# Mic.net
KiCad netlist of a schematic drawn in Altium Designer
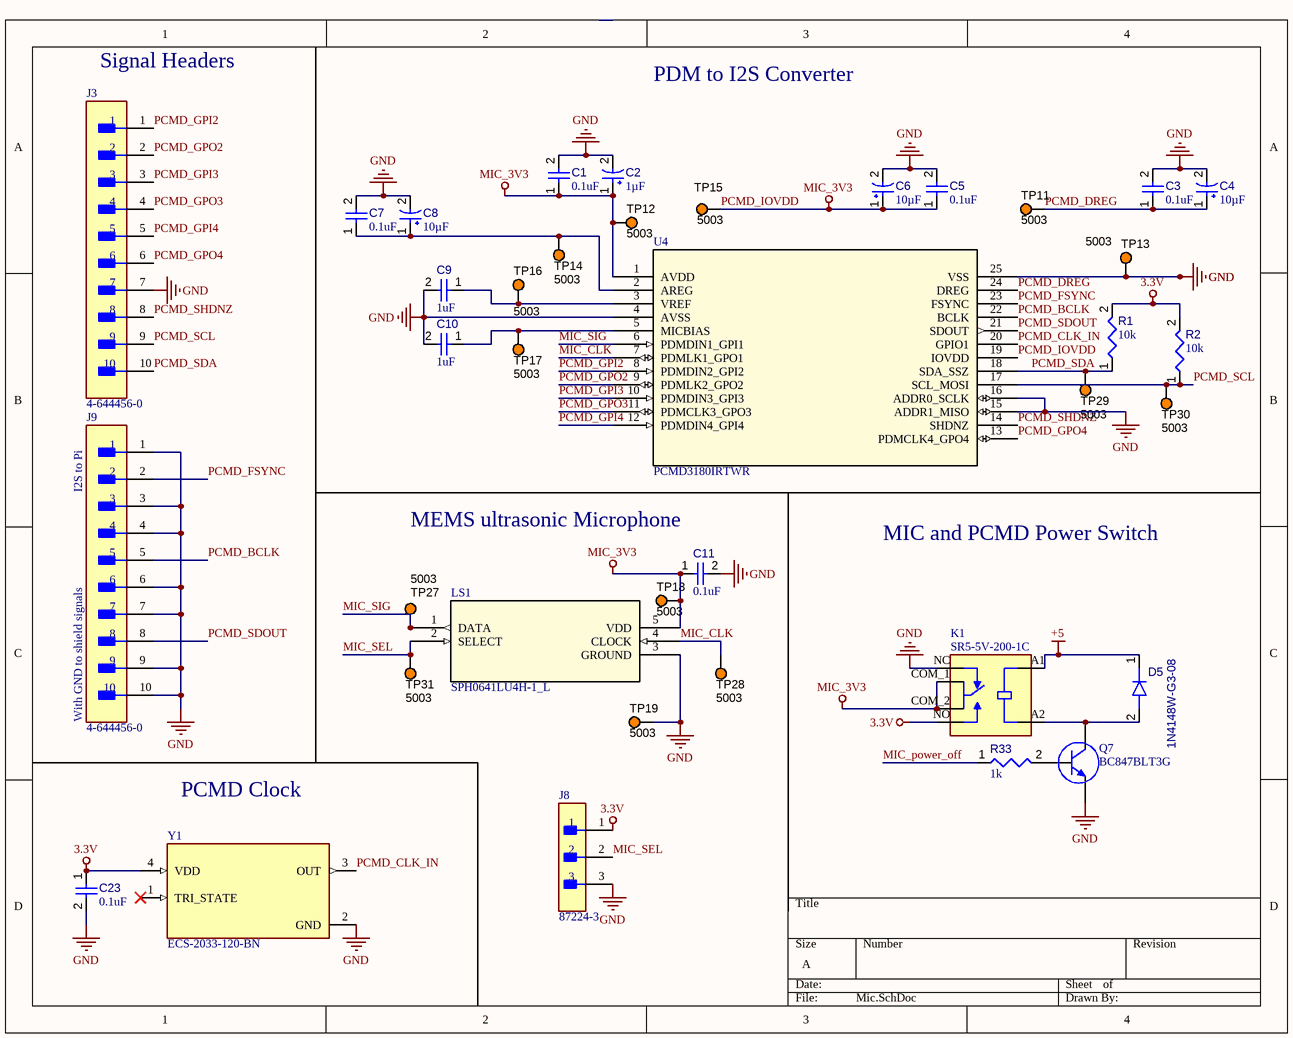
[diagram p0: Mic.SchDoc]

(export (version "E")
  (design (tool "Eeschema 10.0.6"))
  (components
    (comp (ref "C1")
      (value "0.1uF")
      (footprint "CAPC1608X90X40NL10T20")
      (description "Chip Capacitor, 100 nF, +/- 10%, 50 V, 0603 (1608 Metric)")
      (fields (field (name "TOLERANCE") "10%") (field (name "Comment") "Capacitor 100 nF +/-10% 50 V 0603"))
      (libsource (lib "University of Michigan") (part "CAP-NP-2"))
    )
    (comp (ref "C2")
      (value "1µF")
      (footprint "CAPPR55-200-1100X500X1200")
      (description "Aluminum Electrolytic Capacitor, 1 uF, +/- 20%, 50 V, -55 to 105 degC, 2-Pin THD, RoHS, Bulk")
      (fields (field (name "TOLERANCE") "20%") (field (name "MANUFACTURER") "Panasonic"))
      (libsource (lib "University of Michigan") (part "CAP-P-2"))
    )
    (comp (ref "C3")
      (value "0.1uF")
      (footprint "CAPC1608X90X40NL10T20")
      (description "Chip Capacitor, 100 nF, +/- 10%, 50 V, 0603 (1608 Metric)")
      (fields (field (name "TOLERANCE") "10%") (field (name "Comment") "Capacitor 100 nF +/-10% 50 V 0603"))
      (libsource (lib "University of Michigan") (part "CAP-NP-2"))
    )
    (comp (ref "C4")
      (value "10µF")
      (footprint "CAPPR55-200-1100X500X1200")
      (description "Aluminum Electrolytic Capacitor, 1 uF, +/- 20%, 50 V, -55 to 105 degC, 2-Pin THD, RoHS, Bulk")
      (fields (field (name "TOLERANCE") "20%") (field (name "MANUFACTURER") "Panasonic"))
      (libsource (lib "University of Michigan") (part "CAP-P-2"))
    )
    (comp (ref "C5")
      (value "0.1uF")
      (footprint "CAPC1608X90X40NL10T20")
      (description "Chip Capacitor, 100 nF, +/- 10%, 50 V, 0603 (1608 Metric)")
      (fields (field (name "TOLERANCE") "10%") (field (name "Comment") "Capacitor 100 nF +/-10% 50 V 0603"))
      (libsource (lib "University of Michigan") (part "CAP-NP-2"))
    )
    (comp (ref "C6")
      (value "10µF")
      (footprint "CAPPR55-200-1100X500X1200")
      (description "Aluminum Electrolytic Capacitor, 1 uF, +/- 20%, 50 V, -55 to 105 degC, 2-Pin THD, RoHS, Bulk")
      (fields (field (name "TOLERANCE") "20%") (field (name "MANUFACTURER") "Panasonic"))
      (libsource (lib "") (part "CAP-P-2_1"))
    )
    (comp (ref "C7")
      (value "0.1uF")
      (footprint "CAPC1608X90X40NL10T20")
      (description "Chip Capacitor, 100 nF, +/- 10%, 50 V, 0603 (1608 Metric)")
      (fields (field (name "TOLERANCE") "10%") (field (name "Comment") "Capacitor 100 nF +/-10% 50 V 0603"))
      (libsource (lib "University of Michigan") (part "CAP-NP-2"))
    )
    (comp (ref "C8")
      (value "10µF")
      (footprint "CAPPR55-200-1100X500X1200")
      (description "Aluminum Electrolytic Capacitor, 1 uF, +/- 20%, 50 V, -55 to 105 degC, 2-Pin THD, RoHS, Bulk")
      (fields (field (name "TOLERANCE") "20%") (field (name "MANUFACTURER") "Panasonic"))
      (libsource (lib "University of Michigan") (part "CAP-P-2"))
    )
    (comp (ref "C9")
      (value "1uF")
      (footprint "CAPC1608X90X40NL10T20")
      (description "Chip Capacitor, 100 nF, +/- 10%, 50 V, 0603 (1608 Metric)")
      (fields (field (name "TOLERANCE") "10%") (field (name "Comment") "Capacitor 100 nF +/-10% 50 V 0603"))
      (libsource (lib "University of Michigan") (part "CAP-NP-2"))
    )
    (comp (ref "C10")
      (value "1uF")
      (footprint "CAPC1608X90X40NL10T20")
      (description "Chip Capacitor, 100 nF, +/- 10%, 50 V, 0603 (1608 Metric)")
      (fields (field (name "TOLERANCE") "10%") (field (name "Comment") "Capacitor 100 nF +/-10% 50 V 0603"))
      (libsource (lib "University of Michigan") (part "CAP-NP-2"))
    )
    (comp (ref "C11")
      (value "0.1uF")
      (footprint "CAPC1608X90X40NL10T20")
      (description "Chip Capacitor, 100 nF, +/- 10%, 50 V, 0603 (1608 Metric)")
      (fields (field (name "TOLERANCE") "10%") (field (name "Comment") "Capacitor 100 nF +/-10% 50 V 0603"))
      (libsource (lib "University of Michigan") (part "CAP-NP-2"))
    )
    (comp (ref "C23")
      (value "0.1uF")
      (footprint "CAPC1608X90X40NL10T20")
      (description "Chip Capacitor, 100 nF, +/- 10%, 50 V, 0603 (1608 Metric)")
      (fields (field (name "TOLERANCE") "10%") (field (name "Comment") "Capacitor 100 nF +/-10% 50 V 0603"))
      (libsource (lib "University of Michigan") (part "CAP-NP-2"))
    )
    (comp (ref "D5")
      (value "1N4148W-G3-08")
      (footprint "FP-S8-V-3910_01-001-IPC_B")
      (description "Rectifier Diode, 1 Phase, 1 Element, 0.15A, 100V V(RRM), Silicon")
      (libsource (lib "University of Michigan") (part "DIODE-2"))
    )
    (comp (ref "J3")
      (value "4-644456-0")
      (footprint "FP-4-644456-0-MFG")
      (libsource (lib "University of Michigan") (part "aee40dc8b284c03a16094555aa210be"))
    )
    (comp (ref "J8")
      (value "87224-3")
      (footprint "FP-87224-3-MFG")
      (libsource (lib "University of Michigan") (part "0d3f023dd272f625e17a2be33dea85f"))
    )
    (comp (ref "J9")
      (value "4-644456-0")
      (footprint "FP-4-644456-0-MFG")
      (libsource (lib "University of Michigan") (part "aee40dc8b284c03a16094555aa210be"))
    )
    (comp (ref "K1")
      (value "SR5-5V-200-1C")
      (footprint "RELAY_SR5-5V-200-1C")
      (description "15.6 x 10.6 x 11.8 mm, 5 V, 1 A, SPDT (1 Form C), Through Hole, Signal Relay")
      (fields (field (name "MF") "CUI Devices"))
      (libsource (lib "University of Michigan") (part "SR5-5V-200-1C"))
    )
    (comp (ref "LS1")
      (value "SPH0641LU4H-1_L")
      (footprint "SPH0655LM4H-1_KNO_L")
      (description "No Description Available")
      (fields
        (field (name "MANUFACTURER_PART_NUMBER") "SPH0641LU4H-1")
        (field (name "COPYRIGHT") "Copyright (C) 2023 Ultra Librarian. All rights reserved.")
      )
      (libsource (lib "University of Michigan") (part "SPH0641LU4H-1_L"))
    )
    (comp (ref "Q7")
      (value "BC847BLT3G")
      (footprint "ONSC-SOT-23-3-318-08_V")
      (description "Small Signal Bipolar Transistor, 0.1A I(C), 45V V(BR)CEO, 1-Element, NPN, Silicon, TO-236")
      (libsource (lib "University of Michigan") (part "TRANS-NPN-3"))
    )
    (comp (ref "R1")
      (value "10k")
      (footprint "RESC0603(1608)_L")
      (description "Chip Resistor, 120 Ohms, +/-5 %, 0.1 W, -55 to 155 degC, 0603")
      (fields (field (name "POWER") "100mW") (field (name "TOLERANCE") "5%"))
      (libsource (lib "University of Michigan") (part "RES-2"))
    )
    (comp (ref "R2")
      (value "10k")
      (footprint "RESC0603(1608)_L")
      (description "Chip Resistor, 120 Ohms, +/-5 %, 0.1 W, -55 to 155 degC, 0603")
      (fields (field (name "POWER") "100mW") (field (name "TOLERANCE") "5%"))
      (libsource (lib "University of Michigan") (part "RES-2"))
    )
    (comp (ref "R33")
      (value "1k")
      (footprint "RESC0603(1608)_L")
      (description "Chip Resistor, 120 Ohms, +/-5 %, 0.1 W, -55 to 155 degC, 0603")
      (fields (field (name "POWER") "100mW") (field (name "TOLERANCE") "5%"))
      (libsource (lib "University of Michigan") (part "RES-2"))
    )
    (comp (ref "TP11")
      (value "5003")
      (footprint "KSTN-5003")
      (description "Test Point, Orange, Height 4.6 mm, Tail Length 3 mm, 1-Pin THD, RoHS")
      (fields (field (name "MANUFACTURER") "Keystone"))
      (libsource (lib "University of Michigan") (part "TESTPOINT_ORANGE"))
    )
    (comp (ref "TP12")
      (value "5003")
      (footprint "KSTN-5003")
      (description "Test Point, Orange, Height 4.6 mm, Tail Length 3 mm, 1-Pin THD, RoHS")
      (fields (field (name "MANUFACTURER") "Keystone"))
      (libsource (lib "University of Michigan") (part "TESTPOINT_ORANGE"))
    )
    (comp (ref "TP13")
      (value "5003")
      (footprint "KSTN-5003")
      (description "Test Point, Orange, Height 4.6 mm, Tail Length 3 mm, 1-Pin THD, RoHS")
      (fields (field (name "MANUFACTURER") "Keystone"))
      (libsource (lib "University of Michigan") (part "TESTPOINT_ORANGE"))
    )
    (comp (ref "TP14")
      (value "5003")
      (footprint "KSTN-5003")
      (description "Test Point, Orange, Height 4.6 mm, Tail Length 3 mm, 1-Pin THD, RoHS")
      (fields (field (name "MANUFACTURER") "Keystone"))
      (libsource (lib "University of Michigan") (part "TESTPOINT_ORANGE"))
    )
    (comp (ref "TP15")
      (value "5003")
      (footprint "KSTN-5003")
      (description "Test Point, Orange, Height 4.6 mm, Tail Length 3 mm, 1-Pin THD, RoHS")
      (fields (field (name "MANUFACTURER") "Keystone"))
      (libsource (lib "University of Michigan") (part "TESTPOINT_ORANGE"))
    )
    (comp (ref "TP16")
      (value "5003")
      (footprint "KSTN-5003")
      (description "Test Point, Orange, Height 4.6 mm, Tail Length 3 mm, 1-Pin THD, RoHS")
      (fields (field (name "MANUFACTURER") "Keystone"))
      (libsource (lib "University of Michigan") (part "TESTPOINT_ORANGE"))
    )
    (comp (ref "TP17")
      (value "5003")
      (footprint "KSTN-5003")
      (description "Test Point, Orange, Height 4.6 mm, Tail Length 3 mm, 1-Pin THD, RoHS")
      (fields (field (name "MANUFACTURER") "Keystone"))
      (libsource (lib "University of Michigan") (part "TESTPOINT_ORANGE"))
    )
    (comp (ref "TP18")
      (value "5003")
      (footprint "KSTN-5003")
      (description "Test Point, Orange, Height 4.6 mm, Tail Length 3 mm, 1-Pin THD, RoHS")
      (fields (field (name "MANUFACTURER") "Keystone"))
      (libsource (lib "University of Michigan") (part "TESTPOINT_ORANGE"))
    )
    (comp (ref "TP19")
      (value "5003")
      (footprint "KSTN-5003")
      (description "Test Point, Orange, Height 4.6 mm, Tail Length 3 mm, 1-Pin THD, RoHS")
      (fields (field (name "MANUFACTURER") "Keystone"))
      (libsource (lib "University of Michigan") (part "TESTPOINT_ORANGE"))
    )
    (comp (ref "TP27")
      (value "5003")
      (footprint "KSTN-5003")
      (description "Test Point, Orange, Height 4.6 mm, Tail Length 3 mm, 1-Pin THD, RoHS")
      (fields (field (name "MANUFACTURER") "Keystone"))
      (libsource (lib "University of Michigan") (part "TESTPOINT_ORANGE"))
    )
    (comp (ref "TP28")
      (value "5003")
      (footprint "KSTN-5003")
      (description "Test Point, Orange, Height 4.6 mm, Tail Length 3 mm, 1-Pin THD, RoHS")
      (fields (field (name "MANUFACTURER") "Keystone"))
      (libsource (lib "University of Michigan") (part "TESTPOINT_ORANGE"))
    )
    (comp (ref "TP29")
      (value "5003")
      (footprint "KSTN-5003")
      (description "Test Point, Orange, Height 4.6 mm, Tail Length 3 mm, 1-Pin THD, RoHS")
      (fields (field (name "MANUFACTURER") "Keystone"))
      (libsource (lib "University of Michigan") (part "TESTPOINT_ORANGE"))
    )
    (comp (ref "TP30")
      (value "5003")
      (footprint "KSTN-5003")
      (description "Test Point, Orange, Height 4.6 mm, Tail Length 3 mm, 1-Pin THD, RoHS")
      (fields (field (name "MANUFACTURER") "Keystone"))
      (libsource (lib "University of Michigan") (part "TESTPOINT_ORANGE"))
    )
    (comp (ref "TP31")
      (value "5003")
      (footprint "KSTN-5003")
      (description "Test Point, Orange, Height 4.6 mm, Tail Length 3 mm, 1-Pin THD, RoHS")
      (fields (field (name "MANUFACTURER") "Keystone"))
      (libsource (lib "University of Michigan") (part "TESTPOINT_ORANGE"))
    )
    (comp (ref "U4")
      (value "PCMD3180IRTWR")
      (footprint "QFN_0IRTWR_TEX")
      (description "No Description Available")
      (fields (field (name "COPYRIGHT") "Copyright (C) 2023 Ultra Librarian. All rights reserved."))
      (libsource (lib "University of Michigan") (part "PCMD3180IRTWR"))
    )
    (comp (ref "Y1")
      (value "ECS-2033-120-BN")
      (footprint "OSC_ECS-2033-120-BN")
      (description "12MHz XO (Standard) CMOS Oscillator 3.3V Enable/Disable 4-SMD, No Lead")
      (fields (field (name "MF") "ECS Inc."))
      (libsource (lib "University of Michigan") (part "ECS-2033-120-BN"))
    )
  )
  (nets
    (net (code "1") (name "+5") (class "Default")
      (node (ref "D5") (pin "1") (pinfunction "K_1") (pintype "passive"))
      (node (ref "K1") (pin "A1") (pinfunction "COIL1_A1") (pintype "passive"))
    )
    (net (code "2") (name "/MIC_CLK") (class "Default")
      (node (ref "LS1") (pin "4") (pinfunction "CLOCK_4") (pintype "input"))
      (node (ref "TP28") (pin "1") (pinfunction "1_1") (pintype "passive"))
      (node (ref "U4") (pin "7") (pinfunction "PDMLK1_GPO1_7") (pintype "bidirectional"))
    )
    (net (code "3") (name "/MIC_SEL") (class "Default")
      (node (ref "J8") (pin "2") (pinfunction "2_2") (pintype "passive"))
      (node (ref "LS1") (pin "2") (pinfunction "SELECT_2") (pintype "input"))
      (node (ref "TP31") (pin "1") (pinfunction "1_1") (pintype "passive"))
    )
    (net (code "4") (name "/MIC_SIG") (class "Default")
      (node (ref "LS1") (pin "1") (pinfunction "DATA_1") (pintype "output"))
      (node (ref "TP27") (pin "1") (pinfunction "1_1") (pintype "passive"))
      (node (ref "U4") (pin "6") (pinfunction "PDMDIN1_GPI1_6") (pintype "input"))
    )
    (net (code "5") (name "/MIC_power_off") (class "Default")
      (node (ref "R33") (pin "1") (pinfunction "1_1") (pintype "passive"))
    )
    (net (code "6") (name "/PCMD_BCLK") (class "Default")
      (node (ref "J9") (pin "5") (pinfunction "5_5") (pintype "passive"))
      (node (ref "U4") (pin "22") (pinfunction "BCLK_22") (pintype "passive"))
    )
    (net (code "7") (name "/PCMD_CLK_IN") (class "Default")
      (node (ref "U4") (pin "20") (pinfunction "GPIO1_20") (pintype "passive"))
      (node (ref "Y1") (pin "3") (pinfunction "OUT_3") (pintype "output"))
    )
    (net (code "8") (name "/PCMD_DREG") (class "Default")
      (node (ref "C3") (pin "1") (pinfunction "1_1") (pintype "passive"))
      (node (ref "C4") (pin "1") (pinfunction "1_1") (pintype "passive"))
      (node (ref "TP11") (pin "1") (pinfunction "1_1") (pintype "passive"))
      (node (ref "U4") (pin "24") (pinfunction "DREG_24") (pintype "passive"))
    )
    (net (code "9") (name "/PCMD_FSYNC") (class "Default")
      (node (ref "J9") (pin "2") (pinfunction "2_2") (pintype "passive"))
      (node (ref "U4") (pin "23") (pinfunction "FSYNC_23") (pintype "passive"))
    )
    (net (code "10") (name "/PCMD_GPI2") (class "Default")
      (node (ref "J3") (pin "1") (pinfunction "1_1") (pintype "passive"))
      (node (ref "U4") (pin "8") (pinfunction "PDMDIN2_GPI2_8") (pintype "input"))
    )
    (net (code "11") (name "/PCMD_GPI3") (class "Default")
      (node (ref "J3") (pin "3") (pinfunction "3_3") (pintype "passive"))
      (node (ref "U4") (pin "10") (pinfunction "PDMDIN3_GPI3_10") (pintype "input"))
    )
    (net (code "12") (name "/PCMD_GPI4") (class "Default")
      (node (ref "J3") (pin "5") (pinfunction "5_5") (pintype "passive"))
      (node (ref "U4") (pin "12") (pinfunction "PDMDIN4_GPI4_12") (pintype "input"))
    )
    (net (code "13") (name "/PCMD_GPO2") (class "Default")
      (node (ref "J3") (pin "2") (pinfunction "2_2") (pintype "passive"))
      (node (ref "U4") (pin "9") (pinfunction "PDMLK2_GPO2_9") (pintype "bidirectional"))
    )
    (net (code "14") (name "/PCMD_GPO3") (class "Default")
      (node (ref "J3") (pin "4") (pinfunction "4_4") (pintype "passive"))
      (node (ref "U4") (pin "11") (pinfunction "PDMCLK3_GPO3_11") (pintype "bidirectional"))
    )
    (net (code "15") (name "/PCMD_GPO4") (class "Default")
      (node (ref "J3") (pin "6") (pinfunction "6_6") (pintype "passive"))
      (node (ref "U4") (pin "13") (pinfunction "PDMCLK4_GPO4_13") (pintype "bidirectional"))
    )
    (net (code "16") (name "/PCMD_SCL") (class "Default")
      (node (ref "J3") (pin "9") (pinfunction "9_9") (pintype "passive"))
      (node (ref "R2") (pin "1") (pinfunction "1_1") (pintype "passive"))
      (node (ref "TP30") (pin "1") (pinfunction "1_1") (pintype "passive"))
      (node (ref "U4") (pin "17") (pinfunction "SCL_MOSI_17") (pintype "passive"))
    )
    (net (code "17") (name "/PCMD_SDA") (class "Default")
      (node (ref "J3") (pin "10") (pinfunction "10_10") (pintype "passive"))
      (node (ref "R1") (pin "1") (pinfunction "1_1") (pintype "passive"))
      (node (ref "TP29") (pin "1") (pinfunction "1_1") (pintype "passive"))
      (node (ref "U4") (pin "18") (pinfunction "SDA_SSZ_18") (pintype "passive"))
    )
    (net (code "18") (name "/PCMD_SDOUT") (class "Default")
      (node (ref "J9") (pin "8") (pinfunction "8_8") (pintype "passive"))
      (node (ref "U4") (pin "21") (pinfunction "SDOUT_21") (pintype "output"))
    )
    (net (code "19") (name "/PCMD_SHDNZ") (class "Default")
      (node (ref "J3") (pin "8") (pinfunction "8_8") (pintype "passive"))
      (node (ref "U4") (pin "14") (pinfunction "SHDNZ_14") (pintype "passive"))
    )
    (net (code "20") (name "3.3V") (class "Default")
      (node (ref "C23") (pin "1") (pinfunction "1_1") (pintype "passive"))
      (node (ref "J8") (pin "1") (pinfunction "1_1") (pintype "passive"))
      (node (ref "K1") (pin "NO") (pinfunction "NO_NO") (pintype "passive"))
      (node (ref "R1") (pin "2") (pinfunction "2_2") (pintype "passive"))
      (node (ref "R2") (pin "2") (pinfunction "2_2") (pintype "passive"))
      (node (ref "Y1") (pin "4") (pinfunction "VDD_4") (pintype "input"))
    )
    (net (code "21") (name "GND") (class "Default")
      (node (ref "C1") (pin "2") (pinfunction "2_2") (pintype "passive"))
      (node (ref "C10") (pin "2") (pinfunction "2_2") (pintype "passive"))
      (node (ref "C11") (pin "2") (pinfunction "2_2") (pintype "passive"))
      (node (ref "C2") (pin "2") (pinfunction "2_2") (pintype "passive"))
      (node (ref "C23") (pin "2") (pinfunction "2_2") (pintype "passive"))
      (node (ref "C3") (pin "2") (pinfunction "2_2") (pintype "passive"))
      (node (ref "C4") (pin "2") (pinfunction "2_2") (pintype "passive"))
      (node (ref "C5") (pin "2") (pinfunction "2_2") (pintype "passive"))
      (node (ref "C6") (pin "2") (pinfunction "2_2") (pintype "passive"))
      (node (ref "C7") (pin "2") (pinfunction "2_2") (pintype "passive"))
      (node (ref "C8") (pin "2") (pinfunction "2_2") (pintype "passive"))
      (node (ref "C9") (pin "2") (pinfunction "2_2") (pintype "passive"))
      (node (ref "J3") (pin "7") (pinfunction "7_7") (pintype "passive"))
      (node (ref "J8") (pin "3") (pinfunction "3_3") (pintype "passive"))
      (node (ref "J9") (pin "1") (pinfunction "1_1") (pintype "passive"))
      (node (ref "J9") (pin "10") (pinfunction "10_10") (pintype "passive"))
      (node (ref "J9") (pin "3") (pinfunction "3_3") (pintype "passive"))
      (node (ref "J9") (pin "4") (pinfunction "4_4") (pintype "passive"))
      (node (ref "J9") (pin "6") (pinfunction "6_6") (pintype "passive"))
      (node (ref "J9") (pin "7") (pinfunction "7_7") (pintype "passive"))
      (node (ref "J9") (pin "9") (pinfunction "9_9") (pintype "passive"))
      (node (ref "K1") (pin "NC") (pinfunction "NC_NC") (pintype "passive"))
      (node (ref "LS1") (pin "3") (pinfunction "GROUND_3") (pintype "power_in"))
      (node (ref "Q7") (pin "1") (pinfunction "E_1") (pintype "passive"))
      (node (ref "TP13") (pin "1") (pinfunction "1_1") (pintype "passive"))
      (node (ref "TP19") (pin "1") (pinfunction "1_1") (pintype "passive"))
      (node (ref "U4") (pin "15") (pinfunction "ADDR1_MISO_15") (pintype "bidirectional"))
      (node (ref "U4") (pin "16") (pinfunction "ADDR0_SCLK_16") (pintype "bidirectional"))
      (node (ref "U4") (pin "25") (pinfunction "VSS_25") (pintype "power_in"))
      (node (ref "U4") (pin "4") (pinfunction "AVSS_4") (pintype "power_in"))
      (node (ref "Y1") (pin "2") (pinfunction "GND_2") (pintype "power_in"))
    )
    (net (code "22") (name "MIC_3V3") (class "Default")
      (node (ref "C1") (pin "1") (pinfunction "1_1") (pintype "passive"))
      (node (ref "C11") (pin "1") (pinfunction "1_1") (pintype "passive"))
      (node (ref "C2") (pin "1") (pinfunction "1_1") (pintype "passive"))
      (node (ref "C5") (pin "1") (pinfunction "1_1") (pintype "passive"))
      (node (ref "C6") (pin "1") (pinfunction "1_1") (pintype "passive"))
      (node (ref "K1") (pin "COM_1") (pinfunction "COM1_COM_1") (pintype "passive"))
      (node (ref "K1") (pin "COM_2") (pinfunction "COM2_COM_2") (pintype "passive"))
      (node (ref "LS1") (pin "5") (pinfunction "VDD_5") (pintype "power_in"))
      (node (ref "TP12") (pin "1") (pinfunction "1_1") (pintype "passive"))
      (node (ref "TP15") (pin "1") (pinfunction "1_1") (pintype "passive"))
      (node (ref "TP18") (pin "1") (pinfunction "1_1") (pintype "passive"))
      (node (ref "U4") (pin "1") (pinfunction "AVDD_1") (pintype "power_in"))
      (node (ref "U4") (pin "19") (pinfunction "IOVDD_19") (pintype "power_in"))
    )
    (net (code "23") (name "Net-(D5-A)") (class "Default")
      (node (ref "D5") (pin "2") (pinfunction "A_2") (pintype "passive"))
      (node (ref "K1") (pin "A2") (pinfunction "COIL2_A2") (pintype "passive"))
      (node (ref "Q7") (pin "3") (pinfunction "C_3") (pintype "passive"))
    )
    (net (code "24") (name "Net-(Q7-B)") (class "Default")
      (node (ref "Q7") (pin "2") (pinfunction "B_2") (pintype "passive"))
      (node (ref "R33") (pin "2") (pinfunction "2_2") (pintype "passive"))
    )
    (net (code "25") (name "Net-(U4-AREG)") (class "Default")
      (node (ref "C7") (pin "1") (pinfunction "1_1") (pintype "passive"))
      (node (ref "C8") (pin "1") (pinfunction "1_1") (pintype "passive"))
      (node (ref "TP14") (pin "1") (pinfunction "1_1") (pintype "passive"))
      (node (ref "U4") (pin "2") (pinfunction "AREG_2") (pintype "passive"))
    )
    (net (code "26") (name "Net-(U4-MICBIAS)") (class "Default")
      (node (ref "C10") (pin "1") (pinfunction "1_1") (pintype "passive"))
      (node (ref "TP17") (pin "1") (pinfunction "1_1") (pintype "passive"))
      (node (ref "U4") (pin "5") (pinfunction "MICBIAS_5") (pintype "passive"))
    )
    (net (code "27") (name "Net-(U4-VREF)") (class "Default")
      (node (ref "C9") (pin "1") (pinfunction "1_1") (pintype "passive"))
      (node (ref "TP16") (pin "1") (pinfunction "1_1") (pintype "passive"))
      (node (ref "U4") (pin "3") (pinfunction "VREF_3") (pintype "power_in"))
    )
    (net (code "28") (name "unconnected-(Y1-TRI_STATE-Pad1)") (class "Default")
      (node (ref "Y1") (pin "1") (pinfunction "TRI_STATE_1") (pintype "input+no_connect"))
    )
  )
)
